# main_old.net
KiCad netlist of a schematic drawn in EAGLE
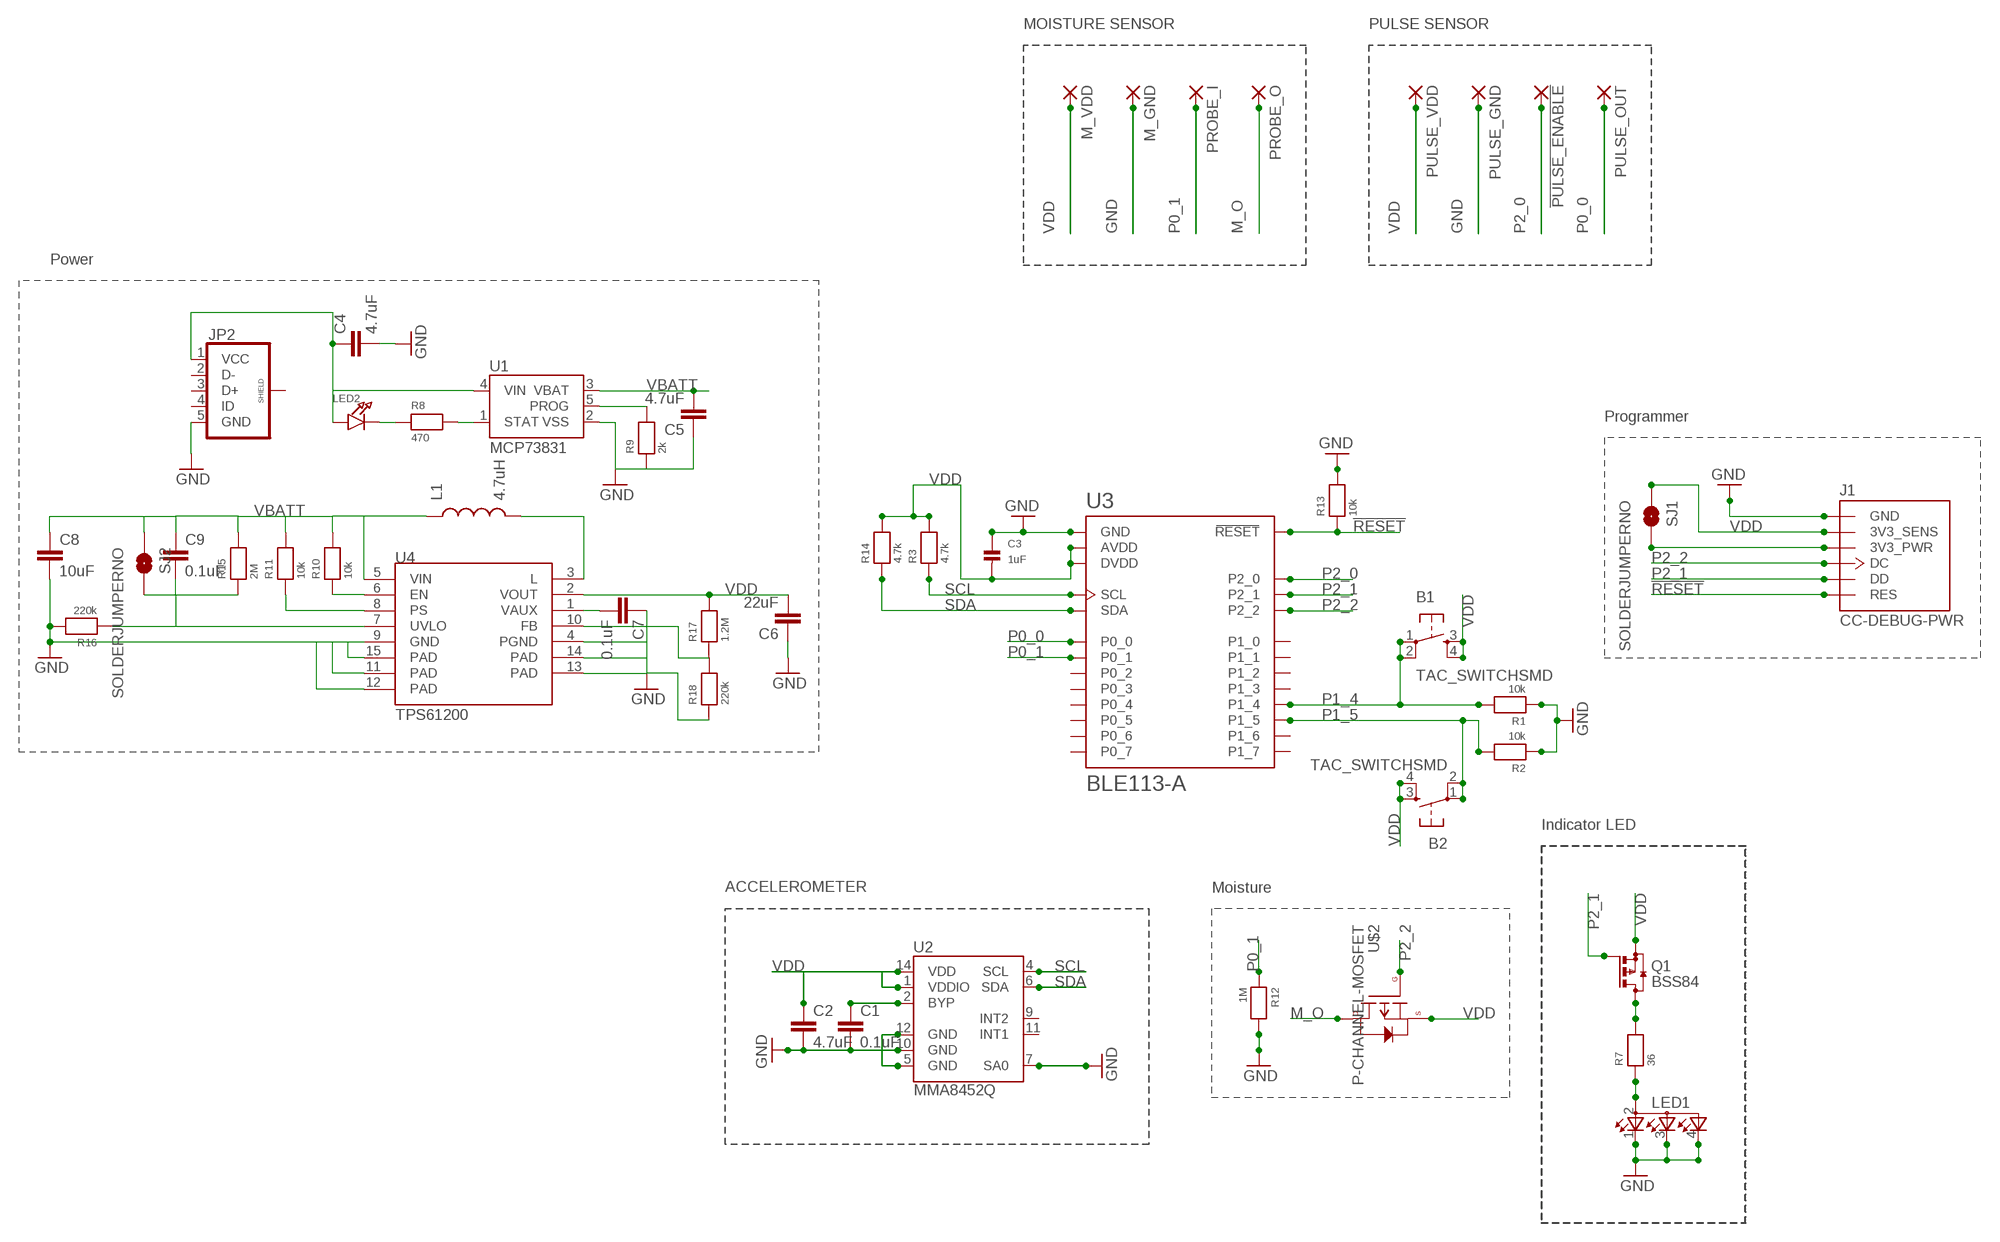
[diagram p0: schematic, sheet 1]

(export (version "E")
  (design (tool "Eeschema 10.0.6"))
  (components
    (comp (ref "!PULSE_ENABLE")
      (value "SMD2")
      (footprint "eagle-import:SMD1,27-2,54")
      (libsource (lib "eagle-import") (part "SMD2"))
    )
    (comp (ref "B1")
      (value "TAC_SWITCHSMD")
      (footprint "eagle-import:TACTILE-SWITCH-SMD")
      (libsource (lib "eagle-import") (part "TAC_SWITCHSMD"))
    )
    (comp (ref "B2")
      (value "TAC_SWITCHSMD")
      (footprint "eagle-import:TACTILE-SWITCH-SMD")
      (libsource (lib "eagle-import") (part "TAC_SWITCHSMD"))
    )
    (comp (ref "C1")
      (value "0.1uF")
      (footprint "eagle-import:0603-CAP")
      (libsource (lib "eagle-import") (part "CAP0603-CAP"))
    )
    (comp (ref "C2")
      (value "4.7uF")
      (footprint "eagle-import:0603-CAP")
      (libsource (lib "eagle-import") (part "CAP0603-CAP"))
    )
    (comp (ref "C3")
      (value "1uF")
      (footprint "eagle-import:0402")
      (libsource (lib "eagle-import") (part "CAP_CERAMIC0402"))
    )
    (comp (ref "C4")
      (value "4.7uF")
      (footprint "eagle-import:0603-CAP")
      (libsource (lib "eagle-import") (part "SparkFun-Passives_CAP0603-CAP"))
    )
    (comp (ref "C5")
      (value "4.7uF")
      (footprint "eagle-import:0603-CAP")
      (libsource (lib "eagle-import") (part "SparkFun-Passives_CAP0603-CAP"))
    )
    (comp (ref "C6")
      (value "22uF")
      (footprint "eagle-import:0603-CAP")
      (libsource (lib "eagle-import") (part "SparkFun-Passives_CAP0603-CAP"))
    )
    (comp (ref "C7")
      (value "0.1uF")
      (footprint "eagle-import:0603-CAP")
      (libsource (lib "eagle-import") (part "SparkFun-Passives_CAP0603-CAP"))
    )
    (comp (ref "C8")
      (value "10uF")
      (footprint "eagle-import:0603-CAP")
      (libsource (lib "eagle-import") (part "SparkFun-Passives_CAP0603-CAP"))
    )
    (comp (ref "C9")
      (value "0.1uF")
      (footprint "eagle-import:0603-CAP")
      (libsource (lib "eagle-import") (part "SparkFun-Passives_CAP0603-CAP"))
    )
    (comp (ref "J1")
      (value "CC-DEBUG-PWR")
      (footprint "eagle-import:CC-P05")
      (libsource (lib "eagle-import") (part "CC-DEBUG-PWR"))
    )
    (comp (ref "JP2")
      (value "USB_MICROB_PLUG-SMT")
      (footprint "eagle-import:MICRO-B-SMT")
      (libsource (lib "eagle-import") (part "USB_MICROB_PLUG-SMT"))
    )
    (comp (ref "L1")
      (value "4.7uH")
      (footprint "eagle-import:0603")
      (libsource (lib "eagle-import") (part "INDUCTOR30OHM,1.8A"))
    )
    (comp (ref "LED1")
      (value "TOPLED-3")
      (footprint "eagle-import:P-LCC-4-3")
      (libsource (lib "eagle-import") (part "TOPLED-3"))
    )
    (comp (ref "LED2")
      (value "LED0603")
      (footprint "eagle-import:CHIPLED_0603")
      (libsource (lib "eagle-import") (part "LED0603"))
    )
    (comp (ref "M_GND")
      (value "SMD2")
      (footprint "eagle-import:SMD1,27-2,54")
      (libsource (lib "eagle-import") (part "SMD2"))
    )
    (comp (ref "M_VDD")
      (value "SMD2")
      (footprint "eagle-import:SMD1,27-2,54")
      (libsource (lib "eagle-import") (part "SMD2"))
    )
    (comp (ref "PROBE_I")
      (value "SMD2")
      (footprint "eagle-import:SMD1,27-2,54")
      (libsource (lib "eagle-import") (part "SMD2"))
    )
    (comp (ref "PROBE_O")
      (value "SMD2")
      (footprint "eagle-import:SMD1,27-2,54")
      (libsource (lib "eagle-import") (part "SMD2"))
    )
    (comp (ref "PULSE_GND")
      (value "SMD2")
      (footprint "eagle-import:SMD1,27-2,54")
      (libsource (lib "eagle-import") (part "SMD2"))
    )
    (comp (ref "PULSE_OUT")
      (value "SMD2")
      (footprint "eagle-import:SMD1,27-2,54")
      (libsource (lib "eagle-import") (part "SMD2"))
    )
    (comp (ref "PULSE_VDD")
      (value "SMD2")
      (footprint "eagle-import:SMD1,27-2,54")
      (libsource (lib "eagle-import") (part "SMD2"))
    )
    (comp (ref "Q1")
      (value "BSS84")
      (footprint "eagle-import:SOT23")
      (libsource (lib "eagle-import") (part "BSS84"))
    )
    (comp (ref "R1")
      (value "10k")
      (footprint "eagle-import:0402")
      (libsource (lib "eagle-import") (part "RESISTOR0402"))
    )
    (comp (ref "R2")
      (value "10k")
      (footprint "eagle-import:0402")
      (libsource (lib "eagle-import") (part "RESISTOR0402"))
    )
    (comp (ref "R3")
      (value "4.7k")
      (footprint "eagle-import:0402")
      (libsource (lib "eagle-import") (part "RESISTOR0402"))
    )
    (comp (ref "R7")
      (value "36")
      (footprint "eagle-import:0402")
      (libsource (lib "eagle-import") (part "RESISTOR0402"))
    )
    (comp (ref "R8")
      (value "470")
      (footprint "eagle-import:0402")
      (libsource (lib "eagle-import") (part "RESISTOR0402"))
    )
    (comp (ref "R9")
      (value "2k")
      (footprint "eagle-import:0402")
      (libsource (lib "eagle-import") (part "RESISTOR0402"))
    )
    (comp (ref "R10")
      (value "10k")
      (footprint "eagle-import:0402")
      (libsource (lib "eagle-import") (part "RESISTOR0402"))
    )
    (comp (ref "R11")
      (value "10k")
      (footprint "eagle-import:0402")
      (libsource (lib "eagle-import") (part "RESISTOR0402"))
    )
    (comp (ref "R12")
      (value "1M")
      (footprint "eagle-import:0402")
      (libsource (lib "eagle-import") (part "RESISTOR0402"))
    )
    (comp (ref "R13")
      (value "10k")
      (footprint "eagle-import:0402")
      (libsource (lib "eagle-import") (part "RESISTOR0402"))
    )
    (comp (ref "R14")
      (value "4.7k")
      (footprint "eagle-import:0402")
      (libsource (lib "eagle-import") (part "RESISTOR0402"))
    )
    (comp (ref "R15")
      (value "2M")
      (footprint "eagle-import:0402")
      (libsource (lib "eagle-import") (part "RESISTOR0402"))
    )
    (comp (ref "R16")
      (value "220k")
      (footprint "eagle-import:0402")
      (libsource (lib "eagle-import") (part "RESISTOR0402"))
    )
    (comp (ref "R17")
      (value "1.2M")
      (footprint "eagle-import:0402")
      (libsource (lib "eagle-import") (part "RESISTOR0402"))
    )
    (comp (ref "R18")
      (value "220k")
      (footprint "eagle-import:0402")
      (libsource (lib "eagle-import") (part "RESISTOR0402"))
    )
    (comp (ref "SJ1")
      (value "SOLDERJUMPERNO")
      (footprint "eagle-import:SJ_2S-NO")
      (libsource (lib "eagle-import") (part "SOLDERJUMPERNO"))
    )
    (comp (ref "SJ2")
      (value "SOLDERJUMPERNO")
      (footprint "eagle-import:SJ_2S-NO")
      (libsource (lib "eagle-import") (part "SOLDERJUMPERNO"))
    )
    (comp (ref "U$2")
      (value "P-CHANNEL-MOSFET")
      (footprint "eagle-import:SOT23-3")
      (libsource (lib "eagle-import") (part "P-CHANNEL-MOSFET"))
    )
    (comp (ref "U1")
      (value "MCP73831")
      (footprint "eagle-import:SOT23-5")
      (libsource (lib "eagle-import") (part "MCP73831"))
    )
    (comp (ref "U2")
      (value "MMA8452Q")
      (footprint "eagle-import:QFN-16_0.5MM")
      (libsource (lib "eagle-import") (part "MMA8452Q"))
    )
    (comp (ref "U3")
      (value "BLE113-A")
      (footprint "eagle-import:BLE113-A")
      (libsource (lib "eagle-import") (part "BLE113-A"))
    )
    (comp (ref "U4")
      (value "TPS61200")
      (footprint "eagle-import:QFN-10_PAD")
      (libsource (lib "eagle-import") (part "TPS61200"))
    )
  )
  (nets
    (net (code "1") (name "/M_O") (class "Default")
      (node (ref "PROBE_O") (pin "1") (pinfunction "P_1") (pintype "passive"))
      (node (ref "U$2") (pin "3") (pinfunction "D_3") (pintype "passive"))
    )
    (net (code "2") (name "/P0_0") (class "Default")
      (node (ref "PULSE_OUT") (pin "1") (pinfunction "P_1") (pintype "passive"))
      (node (ref "U3") (pin "P0_0") (pinfunction "P0_0_P0_0") (pintype "bidirectional"))
    )
    (net (code "3") (name "/P0_1") (class "Default")
      (node (ref "PROBE_I") (pin "1") (pinfunction "P_1") (pintype "passive"))
      (node (ref "R12") (pin "1") (pinfunction "1_1") (pintype "passive"))
      (node (ref "U3") (pin "P0_1") (pinfunction "P0_1_P0_1") (pintype "bidirectional"))
    )
    (net (code "4") (name "/P1_4") (class "Default")
      (node (ref "B1") (pin "1") (pinfunction "1_1") (pintype "passive"))
      (node (ref "B1") (pin "2") (pinfunction "2_2") (pintype "passive"))
      (node (ref "R1") (pin "2") (pinfunction "2_2") (pintype "passive"))
      (node (ref "U3") (pin "P1_4") (pinfunction "P1_4_P1_4") (pintype "bidirectional"))
    )
    (net (code "5") (name "/P1_5") (class "Default")
      (node (ref "B2") (pin "1") (pinfunction "1_1") (pintype "passive"))
      (node (ref "B2") (pin "2") (pinfunction "2_2") (pintype "passive"))
      (node (ref "R2") (pin "2") (pinfunction "2_2") (pintype "passive"))
      (node (ref "U3") (pin "P1_5") (pinfunction "P1_5_P1_5") (pintype "bidirectional"))
    )
    (net (code "6") (name "/P2_0") (class "Default")
      (node (ref "!PULSE_ENABLE") (pin "1") (pinfunction "P_1") (pintype "passive"))
      (node (ref "U3") (pin "P2_0") (pinfunction "P2_0_P2_0") (pintype "bidirectional"))
    )
    (net (code "7") (name "/P2_1") (class "Default")
      (node (ref "J1") (pin "4") (pinfunction "DD_4") (pintype "bidirectional"))
      (node (ref "Q1") (pin "1") (pinfunction "G_1") (pintype "passive"))
      (node (ref "U3") (pin "P2_1") (pinfunction "P2_1_P2_1") (pintype "bidirectional"))
    )
    (net (code "8") (name "/P2_2") (class "Default")
      (node (ref "J1") (pin "3") (pinfunction "DC_3") (pintype "output"))
      (node (ref "U$2") (pin "1") (pinfunction "G_1") (pintype "passive"))
      (node (ref "U3") (pin "P2_2") (pinfunction "P2_2_P2_2") (pintype "bidirectional"))
    )
    (net (code "9") (name "/SCL") (class "Default")
      (node (ref "R3") (pin "1") (pinfunction "1_1") (pintype "passive"))
      (node (ref "U2") (pin "4") (pinfunction "SCL_4") (pintype "bidirectional"))
      (node (ref "U3") (pin "SCL") (pinfunction "SCL_SCL") (pintype "bidirectional"))
    )
    (net (code "10") (name "/SDA") (class "Default")
      (node (ref "R14") (pin "1") (pinfunction "1_1") (pintype "passive"))
      (node (ref "U2") (pin "6") (pinfunction "SDA_6") (pintype "bidirectional"))
      (node (ref "U3") (pin "SDA") (pinfunction "SDA_SDA") (pintype "bidirectional"))
    )
    (net (code "11") (name "/VBATT") (class "Default")
      (node (ref "C5") (pin "2") (pinfunction "2_2") (pintype "passive"))
      (node (ref "C8") (pin "1") (pinfunction "1_1") (pintype "passive"))
      (node (ref "C9") (pin "1") (pinfunction "1_1") (pintype "passive"))
      (node (ref "L1") (pin "1") (pinfunction "1_1") (pintype "passive"))
      (node (ref "R10") (pin "2") (pinfunction "2_2") (pintype "passive"))
      (node (ref "R11") (pin "2") (pinfunction "2_2") (pintype "passive"))
      (node (ref "R15") (pin "2") (pinfunction "2_2") (pintype "passive"))
      (node (ref "SJ2") (pin "1") (pinfunction "1_1") (pintype "passive"))
      (node (ref "U1") (pin "3") (pinfunction "VBAT_3") (pintype "power_in"))
      (node (ref "U4") (pin "5") (pinfunction "VIN_5") (pintype "power_in"))
    )
    (net (code "12") (name "/VDD") (class "Default")
      (node (ref "B1") (pin "3") (pinfunction "3_3") (pintype "passive"))
      (node (ref "B1") (pin "4") (pinfunction "4_4") (pintype "passive"))
      (node (ref "B2") (pin "3") (pinfunction "3_3") (pintype "passive"))
      (node (ref "B2") (pin "4") (pinfunction "4_4") (pintype "passive"))
      (node (ref "C2") (pin "1") (pinfunction "1_1") (pintype "passive"))
      (node (ref "C3") (pin "2") (pinfunction "P$2_2") (pintype "passive"))
      (node (ref "C6") (pin "2") (pinfunction "2_2") (pintype "passive"))
      (node (ref "J1") (pin "2") (pinfunction "3V3_SENS_2") (pintype "power_in"))
      (node (ref "M_VDD") (pin "1") (pinfunction "P_1") (pintype "passive"))
      (node (ref "PULSE_VDD") (pin "1") (pinfunction "P_1") (pintype "passive"))
      (node (ref "Q1") (pin "2") (pinfunction "S_2") (pintype "passive"))
      (node (ref "R14") (pin "2") (pinfunction "2_2") (pintype "passive"))
      (node (ref "R17") (pin "2") (pinfunction "2_2") (pintype "passive"))
      (node (ref "R3") (pin "2") (pinfunction "2_2") (pintype "passive"))
      (node (ref "SJ1") (pin "1") (pinfunction "1_1") (pintype "passive"))
      (node (ref "U$2") (pin "2") (pinfunction "S_2") (pintype "passive"))
      (node (ref "U2") (pin "1") (pinfunction "VDDIO_1") (pintype "bidirectional"))
      (node (ref "U2") (pin "14") (pinfunction "VDD_14") (pintype "bidirectional"))
      (node (ref "U3") (pin "AVDD") (pinfunction "AVDD_AVDD") (pintype "power_in"))
      (node (ref "U3") (pin "DVDD") (pinfunction "DVDD_DVDD") (pintype "power_in"))
      (node (ref "U4") (pin "2") (pinfunction "VOUT_2") (pintype "passive"))
    )
    (net (code "13") (name "/~{RESET}") (class "Default")
      (node (ref "J1") (pin "7") (pinfunction "RES_7") (pintype "output"))
      (node (ref "R13") (pin "1") (pinfunction "1_1") (pintype "passive"))
      (node (ref "U3") (pin "RESET") (pinfunction "RESET_RESET") (pintype "input"))
    )
    (net (code "14") (name "GND") (class "Default")
      (node (ref "C1") (pin "2") (pinfunction "2_2") (pintype "passive"))
      (node (ref "C2") (pin "2") (pinfunction "2_2") (pintype "passive"))
      (node (ref "C3") (pin "1") (pinfunction "P$1_1") (pintype "passive"))
      (node (ref "C4") (pin "2") (pinfunction "2_2") (pintype "passive"))
      (node (ref "C5") (pin "1") (pinfunction "1_1") (pintype "passive"))
      (node (ref "C6") (pin "1") (pinfunction "1_1") (pintype "passive"))
      (node (ref "C7") (pin "1") (pinfunction "1_1") (pintype "passive"))
      (node (ref "C8") (pin "2") (pinfunction "2_2") (pintype "passive"))
      (node (ref "J1") (pin "1") (pinfunction "GND_1") (pintype "power_in"))
      (node (ref "JP2") (pin "5") (pinfunction "GND_5") (pintype "bidirectional"))
      (node (ref "LED1") (pin "1") (pinfunction "CRED_1") (pintype "passive"))
      (node (ref "LED1") (pin "3") (pinfunction "CBLUE_3") (pintype "passive"))
      (node (ref "LED1") (pin "4") (pinfunction "CGREEN_4") (pintype "passive"))
      (node (ref "M_GND") (pin "1") (pinfunction "P_1") (pintype "passive"))
      (node (ref "PULSE_GND") (pin "1") (pinfunction "P_1") (pintype "passive"))
      (node (ref "R1") (pin "1") (pinfunction "1_1") (pintype "passive"))
      (node (ref "R12") (pin "2") (pinfunction "2_2") (pintype "passive"))
      (node (ref "R13") (pin "2") (pinfunction "2_2") (pintype "passive"))
      (node (ref "R16") (pin "2") (pinfunction "2_2") (pintype "passive"))
      (node (ref "R18") (pin "1") (pinfunction "1_1") (pintype "passive"))
      (node (ref "R2") (pin "1") (pinfunction "1_1") (pintype "passive"))
      (node (ref "R9") (pin "1") (pinfunction "1_1") (pintype "passive"))
      (node (ref "U1") (pin "2") (pinfunction "VSS_2") (pintype "power_in"))
      (node (ref "U2") (pin "10") (pinfunction "GND_10") (pintype "bidirectional"))
      (node (ref "U2") (pin "12") (pinfunction "GND_12") (pintype "bidirectional"))
      (node (ref "U2") (pin "5") (pinfunction "GND_5") (pintype "bidirectional"))
      (node (ref "U2") (pin "7") (pinfunction "SA0_7") (pintype "bidirectional"))
      (node (ref "U3") (pin "GND") (pinfunction "GND_GND") (pintype "power_in"))
      (node (ref "U3") (pin "GND@10") (pinfunction "GND_GND@10") (pintype "power_in"))
      (node (ref "U3") (pin "GND@2") (pinfunction "GND_GND@2") (pintype "power_in"))
      (node (ref "U3") (pin "GND@3") (pinfunction "GND_GND@3") (pintype "power_in"))
      (node (ref "U3") (pin "GND@4") (pinfunction "GND_GND@4") (pintype "power_in"))
      (node (ref "U3") (pin "GND@5") (pinfunction "GND_GND@5") (pintype "power_in"))
      (node (ref "U3") (pin "GND@6") (pinfunction "GND_GND@6") (pintype "power_in"))
      (node (ref "U3") (pin "GND@7") (pinfunction "GND_GND@7") (pintype "power_in"))
      (node (ref "U3") (pin "GND@8") (pinfunction "GND_GND@8") (pintype "power_in"))
      (node (ref "U3") (pin "GND@9") (pinfunction "GND_GND@9") (pintype "power_in"))
      (node (ref "U4") (pin "11") (pinfunction "PAD_11") (pintype "power_in"))
      (node (ref "U4") (pin "12") (pinfunction "PAD_12") (pintype "power_in"))
      (node (ref "U4") (pin "13") (pinfunction "PAD_13") (pintype "power_in"))
      (node (ref "U4") (pin "14") (pinfunction "PAD_14") (pintype "power_in"))
      (node (ref "U4") (pin "15") (pinfunction "PAD_15") (pintype "power_in"))
      (node (ref "U4") (pin "4") (pinfunction "PGND_4") (pintype "power_in"))
      (node (ref "U4") (pin "9") (pinfunction "GND_9") (pintype "power_in"))
    )
    (net (code "15") (name "Net-(J1-3V3_PWR)") (class "Default")
      (node (ref "J1") (pin "9") (pinfunction "3V3_PWR_9") (pintype "power_in"))
      (node (ref "SJ1") (pin "2") (pinfunction "2_2") (pintype "passive"))
    )
    (net (code "16") (name "Net-(JP2-VCC)") (class "Default")
      (node (ref "C4") (pin "1") (pinfunction "1_1") (pintype "passive"))
      (node (ref "JP2") (pin "1") (pinfunction "VCC_1") (pintype "bidirectional"))
      (node (ref "LED2") (pin "A") (pinfunction "A_A") (pintype "passive"))
      (node (ref "U1") (pin "4") (pinfunction "VIN_4") (pintype "power_in"))
    )
    (net (code "17") (name "Net-(LED1-A2)") (class "Default")
      (node (ref "LED1") (pin "2") (pinfunction "A2_2") (pintype "passive"))
      (node (ref "R7") (pin "1") (pinfunction "1_1") (pintype "passive"))
    )
    (net (code "18") (name "Net-(LED2-PadC)") (class "Default")
      (node (ref "LED2") (pin "C") (pinfunction "C_C") (pintype "passive"))
      (node (ref "R8") (pin "1") (pinfunction "1_1") (pintype "passive"))
    )
    (net (code "19") (name "Net-(Q1-D)") (class "Default")
      (node (ref "Q1") (pin "3") (pinfunction "D_3") (pintype "passive"))
      (node (ref "R7") (pin "2") (pinfunction "2_2") (pintype "passive"))
    )
    (net (code "20") (name "Net-(U1-PROG)") (class "Default")
      (node (ref "R9") (pin "2") (pinfunction "2_2") (pintype "passive"))
      (node (ref "U1") (pin "5") (pinfunction "PROG_5") (pintype "input"))
    )
    (net (code "21") (name "Net-(U1-STAT)") (class "Default")
      (node (ref "R8") (pin "2") (pinfunction "2_2") (pintype "passive"))
      (node (ref "U1") (pin "1") (pinfunction "STAT_1") (pintype "output"))
    )
    (net (code "22") (name "Net-(U2-BYP)") (class "Default")
      (node (ref "C1") (pin "1") (pinfunction "1_1") (pintype "passive"))
      (node (ref "U2") (pin "2") (pinfunction "BYP_2") (pintype "bidirectional"))
    )
    (net (code "23") (name "Net-(U4-EN)") (class "Default")
      (node (ref "R10") (pin "1") (pinfunction "1_1") (pintype "passive"))
      (node (ref "U4") (pin "6") (pinfunction "EN_6") (pintype "input"))
    )
    (net (code "24") (name "Net-(U4-FB)") (class "Default")
      (node (ref "R17") (pin "1") (pinfunction "1_1") (pintype "passive"))
      (node (ref "R18") (pin "2") (pinfunction "2_2") (pintype "passive"))
      (node (ref "U4") (pin "10") (pinfunction "FB_10") (pintype "passive"))
    )
    (net (code "25") (name "Net-(U4-L)") (class "Default")
      (node (ref "L1") (pin "2") (pinfunction "2_2") (pintype "passive"))
      (node (ref "U4") (pin "3") (pinfunction "L_3") (pintype "passive"))
    )
    (net (code "26") (name "Net-(U4-PS)") (class "Default")
      (node (ref "R11") (pin "1") (pinfunction "1_1") (pintype "passive"))
      (node (ref "U4") (pin "8") (pinfunction "PS_8") (pintype "input"))
    )
    (net (code "27") (name "Net-(U4-UVLO)") (class "Default")
      (node (ref "C9") (pin "2") (pinfunction "2_2") (pintype "passive"))
      (node (ref "R15") (pin "1") (pinfunction "1_1") (pintype "passive"))
      (node (ref "R16") (pin "1") (pinfunction "1_1") (pintype "passive"))
      (node (ref "SJ2") (pin "2") (pinfunction "2_2") (pintype "passive"))
      (node (ref "U4") (pin "7") (pinfunction "UVLO_7") (pintype "passive"))
    )
    (net (code "28") (name "Net-(U4-VAUX)") (class "Default")
      (node (ref "C7") (pin "2") (pinfunction "2_2") (pintype "passive"))
      (node (ref "U4") (pin "1") (pinfunction "VAUX_1") (pintype "passive"))
    )
    (net (code "29") (name "unconnected-(JP2-D+-Pad3)") (class "Default")
      (node (ref "JP2") (pin "3") (pinfunction "D+_3") (pintype "bidirectional"))
    )
    (net (code "30") (name "unconnected-(JP2-D--Pad2)") (class "Default")
      (node (ref "JP2") (pin "2") (pinfunction "D-_2") (pintype "bidirectional"))
    )
    (net (code "31") (name "unconnected-(JP2-ID-Pad4)") (class "Default")
      (node (ref "JP2") (pin "4") (pinfunction "ID_4") (pintype "bidirectional"))
    )
    (net (code "32") (name "unconnected-(JP2-SHIELD-PadP$6)") (class "Default")
      (node (ref "JP2") (pin "P$6") (pinfunction "SHIELD_P$6") (pintype "bidirectional"))
    )
    (net (code "33") (name "unconnected-(U2-INT1-Pad11)") (class "Default")
      (node (ref "U2") (pin "11") (pinfunction "INT1_11") (pintype "bidirectional"))
    )
    (net (code "34") (name "unconnected-(U2-INT2-Pad9)") (class "Default")
      (node (ref "U2") (pin "9") (pinfunction "INT2_9") (pintype "bidirectional"))
    )
    (net (code "35") (name "unconnected-(U3-PadP0_2)") (class "Default")
      (node (ref "U3") (pin "P0_2") (pinfunction "P0_2_P0_2") (pintype "bidirectional"))
    )
    (net (code "36") (name "unconnected-(U3-PadP0_3)") (class "Default")
      (node (ref "U3") (pin "P0_3") (pinfunction "P0_3_P0_3") (pintype "bidirectional"))
    )
    (net (code "37") (name "unconnected-(U3-PadP0_4)") (class "Default")
      (node (ref "U3") (pin "P0_4") (pinfunction "P0_4_P0_4") (pintype "bidirectional"))
    )
    (net (code "38") (name "unconnected-(U3-PadP0_5)") (class "Default")
      (node (ref "U3") (pin "P0_5") (pinfunction "P0_5_P0_5") (pintype "bidirectional"))
    )
    (net (code "39") (name "unconnected-(U3-PadP0_6)") (class "Default")
      (node (ref "U3") (pin "P0_6") (pinfunction "P0_6_P0_6") (pintype "bidirectional"))
    )
    (net (code "40") (name "unconnected-(U3-PadP0_7)") (class "Default")
      (node (ref "U3") (pin "P0_7") (pinfunction "P0_7_P0_7") (pintype "bidirectional"))
    )
    (net (code "41") (name "unconnected-(U3-PadP1_0)") (class "Default")
      (node (ref "U3") (pin "P1_0") (pinfunction "P1_0_P1_0") (pintype "bidirectional"))
    )
    (net (code "42") (name "unconnected-(U3-PadP1_1)") (class "Default")
      (node (ref "U3") (pin "P1_1") (pinfunction "P1_1_P1_1") (pintype "bidirectional"))
    )
    (net (code "43") (name "unconnected-(U3-PadP1_2)") (class "Default")
      (node (ref "U3") (pin "P1_2") (pinfunction "P1_2_P1_2") (pintype "bidirectional"))
    )
    (net (code "44") (name "unconnected-(U3-PadP1_3)") (class "Default")
      (node (ref "U3") (pin "P1_3") (pinfunction "P1_3_P1_3") (pintype "bidirectional"))
    )
    (net (code "45") (name "unconnected-(U3-PadP1_6)") (class "Default")
      (node (ref "U3") (pin "P1_6") (pinfunction "P1_6_P1_6") (pintype "bidirectional"))
    )
    (net (code "46") (name "unconnected-(U3-PadP1_7)") (class "Default")
      (node (ref "U3") (pin "P1_7") (pinfunction "P1_7_P1_7") (pintype "bidirectional"))
    )
  )
)
